# OSO-RING-A2-01.net
KiCad netlist of a schematic drawn in EAGLE
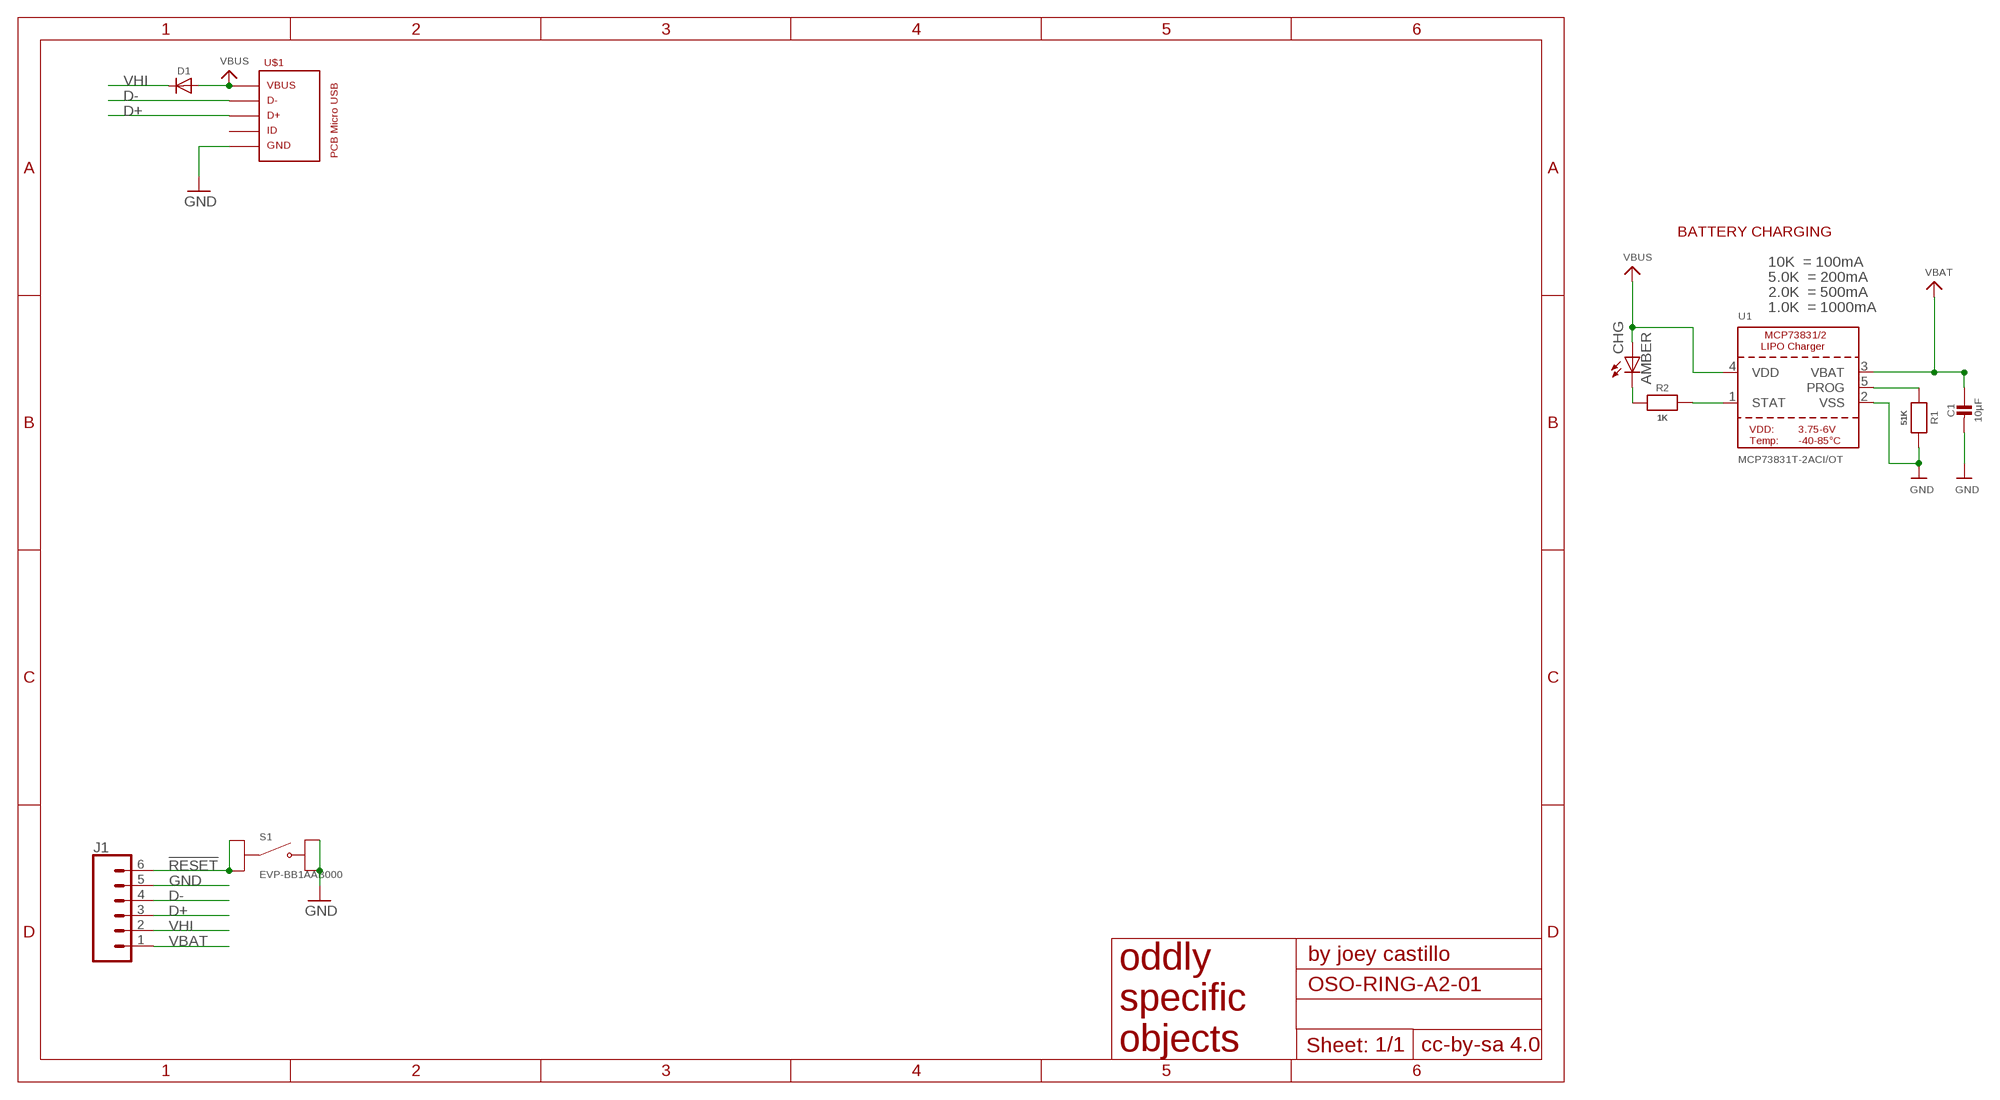
[diagram p0: schematic, sheet 1]

(export (version "E")
  (design (tool "Eeschema 10.0.6"))
  (components
    (comp (ref "C1")
      (value "10µF")
      (footprint "eagle-import:0603-NO")
      (libsource (lib "eagle-import") (part "CAP_CERAMIC0603_NO"))
    )
    (comp (ref "CHG")
      (value "AMBER")
      (footprint "eagle-import:CHIPLED_0805")
      (libsource (lib "eagle-import") (part "LEDCHIPLED_0805"))
    )
    (comp (ref "D1")
      (value "MICROBUILDER_DIODESOD-323")
      (footprint "eagle-import:MICROBUILDER_SOD-323")
      (libsource (lib "eagle-import") (part "MICROBUILDER_DIODESOD-323"))
    )
    (comp (ref "J1")
      (value "CONN_06SMD-1MM")
      (footprint "eagle-import:1X06-1MM")
      (libsource (lib "eagle-import") (part "CONN_06SMD-1MM"))
    )
    (comp (ref "R1")
      (value "51K")
      (footprint "eagle-import:0603-NO")
      (libsource (lib "eagle-import") (part "RESISTOR_0603_NOOUT"))
    )
    (comp (ref "R2")
      (value "1K")
      (footprint "eagle-import:0603-NO")
      (libsource (lib "eagle-import") (part "RESISTOR_0603_NOOUT"))
    )
    (comp (ref "S1")
      (value "EVP-BB1AAB000")
      (footprint "eagle-import:SW_EVP-BB1AAB000")
      (fields
        (field (name "DIGI-KEY_PART_NUMBER") "P124390CT-ND")
        (field (name "MF") "Panasonic Electronic Components")
      )
      (libsource (lib "eagle-import") (part "EVP-BB1AAB000"))
    )
    (comp (ref "U$1")
      (value "PCB_MICRO_USB_BSS_100")
      (footprint "eagle-import:USB_TYPE_B_SS_100")
      (libsource (lib "eagle-import") (part "PCB_MICRO_USB_BSS_100"))
    )
    (comp (ref "U1")
      (value "MCP73831T-2ACI/OT")
      (footprint "eagle-import:SOT23-5")
      (libsource (lib "eagle-import") (part "MCP73831/2"))
    )
  )
  (nets
    (net (code "1") (name "/D+") (class "Default")
      (node (ref "J1") (pin "3") (pinfunction "3_3") (pintype "passive"))
      (node (ref "U$1") (pin "3") (pinfunction "3_3") (pintype "bidirectional"))
    )
    (net (code "2") (name "/D-") (class "Default")
      (node (ref "J1") (pin "4") (pinfunction "4_4") (pintype "passive"))
      (node (ref "U$1") (pin "2") (pinfunction "2_2") (pintype "bidirectional"))
    )
    (net (code "3") (name "/VHI") (class "Default")
      (node (ref "D1") (pin "C") (pinfunction "C_C") (pintype "passive"))
      (node (ref "J1") (pin "2") (pinfunction "2_2") (pintype "passive"))
    )
    (net (code "4") (name "/~{RESET}") (class "Default")
      (node (ref "J1") (pin "6") (pinfunction "6_6") (pintype "passive"))
      (node (ref "S1") (pin "A1") (pinfunction "A1_A1") (pintype "passive"))
      (node (ref "S1") (pin "A2") (pinfunction "A2_A2") (pintype "passive"))
    )
    (net (code "5") (name "GND") (class "Default")
      (node (ref "C1") (pin "2") (pinfunction "2_2") (pintype "passive"))
      (node (ref "J1") (pin "5") (pinfunction "5_5") (pintype "passive"))
      (node (ref "R1") (pin "2") (pinfunction "2_2") (pintype "passive"))
      (node (ref "S1") (pin "B1") (pinfunction "B1_B1") (pintype "passive"))
      (node (ref "S1") (pin "B2") (pinfunction "B2_B2") (pintype "passive"))
      (node (ref "U$1") (pin "5") (pinfunction "5_5") (pintype "bidirectional"))
      (node (ref "U1") (pin "2") (pinfunction "VSS_2") (pintype "power_in"))
    )
    (net (code "6") (name "Net-(CHG-PadC)") (class "Default")
      (node (ref "CHG") (pin "C") (pinfunction "C_C") (pintype "passive"))
      (node (ref "R2") (pin "1") (pinfunction "1_1") (pintype "passive"))
    )
    (net (code "7") (name "Net-(U1-PROG)") (class "Default")
      (node (ref "R1") (pin "1") (pinfunction "1_1") (pintype "passive"))
      (node (ref "U1") (pin "5") (pinfunction "PROG_5") (pintype "input"))
    )
    (net (code "8") (name "Net-(U1-STAT)") (class "Default")
      (node (ref "R2") (pin "2") (pinfunction "2_2") (pintype "passive"))
      (node (ref "U1") (pin "1") (pinfunction "STAT_1") (pintype "output"))
    )
    (net (code "9") (name "VBAT") (class "Default")
      (node (ref "C1") (pin "1") (pinfunction "1_1") (pintype "passive"))
      (node (ref "J1") (pin "1") (pinfunction "1_1") (pintype "passive"))
      (node (ref "U1") (pin "3") (pinfunction "VBAT_3") (pintype "power_in"))
    )
    (net (code "10") (name "VBUS") (class "Default")
      (node (ref "CHG") (pin "A") (pinfunction "A_A") (pintype "passive"))
      (node (ref "D1") (pin "A") (pinfunction "A_A") (pintype "passive"))
      (node (ref "U$1") (pin "1") (pinfunction "1_1") (pintype "bidirectional"))
      (node (ref "U1") (pin "4") (pinfunction "VDD_4") (pintype "power_in"))
    )
    (net (code "11") (name "unconnected-(U$1-Pad4)") (class "Default")
      (node (ref "U$1") (pin "4") (pinfunction "4_4") (pintype "bidirectional"))
    )
  )
)
